# brick_i2c_humidity.net
KiCad netlist of a schematic drawn in EAGLE
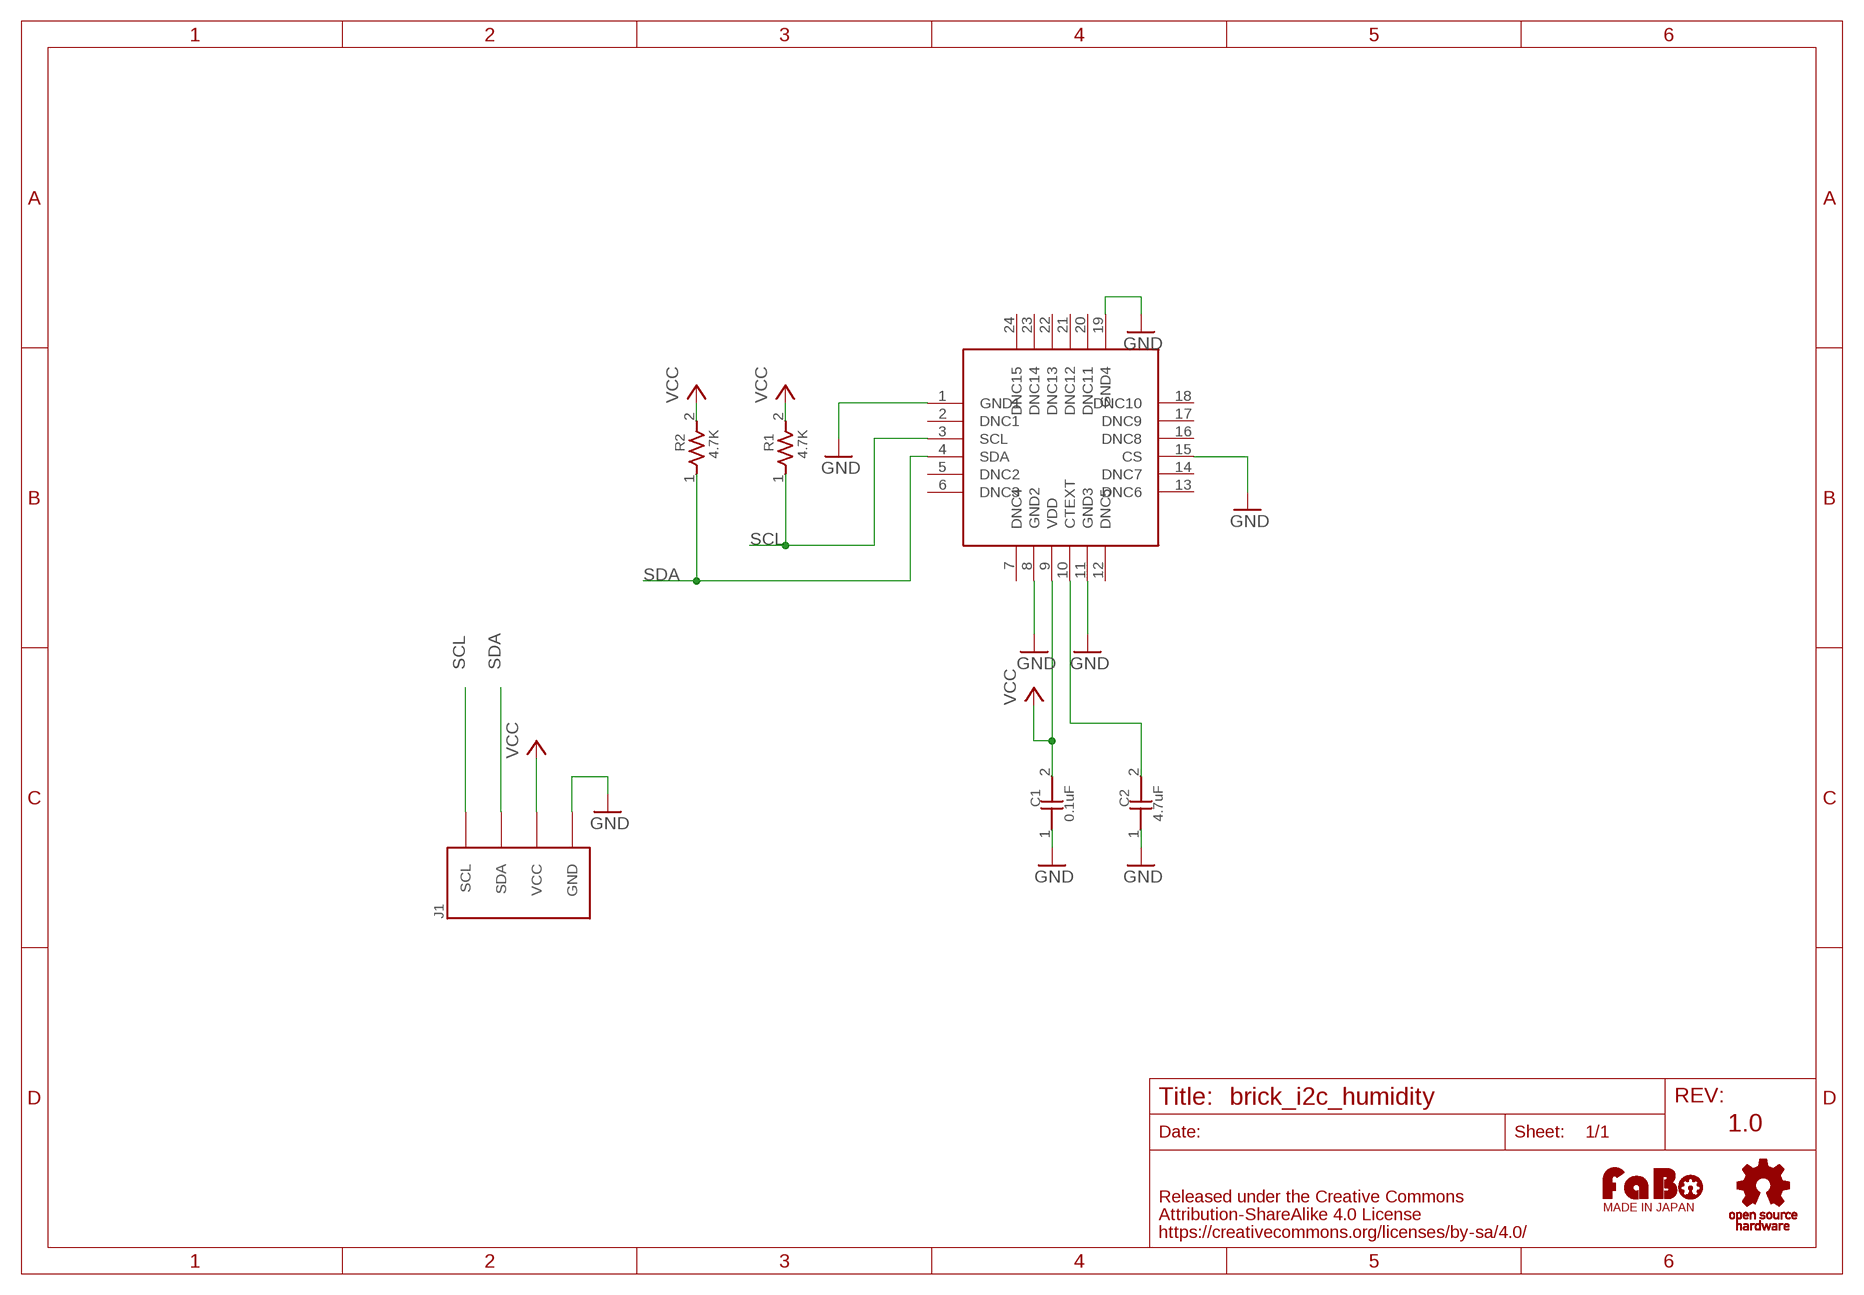
[diagram p0: schematic, sheet 1]

(export (version "E")
  (design (tool "Eeschema 10.0.6"))
  (components
    (comp (ref "C1")
      (value "0.1uF")
      (footprint "eagle-import:0603")
      (libsource (lib "eagle-import") (part "CAPACITOR0603"))
    )
    (comp (ref "C2")
      (value "4.7uF")
      (footprint "eagle-import:0603")
      (libsource (lib "eagle-import") (part "CAPACITOR0603"))
    )
    (comp (ref "J1")
      (value "BRICK_I2C")
      (footprint "eagle-import:BRICK_I2C")
      (libsource (lib "eagle-import") (part "BRICK_I2C"))
    )
    (comp (ref "R1")
      (value "4.7K")
      (footprint "eagle-import:0603")
      (libsource (lib "eagle-import") (part "RESISTOR0603"))
    )
    (comp (ref "R2")
      (value "4.7K")
      (footprint "eagle-import:0603")
      (libsource (lib "eagle-import") (part "RESISTOR0603"))
    )
    (comp (ref "SI1")
      (value "SILICONLAB-SI7005")
      (footprint "eagle-import:SILICONLAB-SI7005")
      (libsource (lib "eagle-import") (part "SILICONLAB-SI7005"))
    )
    (comp (ref "U$2")
      (value "LOGO_FABO-M")
      (footprint "eagle-import:LOGO_FABO_M")
      (libsource (lib "eagle-import") (part "LOGO_FABO-M"))
    )
    (comp (ref "U$4")
      (value "LOGO_OSHW_T-M")
      (footprint "eagle-import:LOGO_OSHW_T_M")
      (libsource (lib "eagle-import") (part "LOGO_OSHW_T-M"))
    )
  )
  (nets
    (net (code "1") (name "/SCL") (class "Default")
      (node (ref "J1") (pin "SCL") (pinfunction "SCL_SCL") (pintype "bidirectional"))
      (node (ref "R1") (pin "1") (pinfunction "1_1") (pintype "passive"))
      (node (ref "SI1") (pin "3") (pinfunction "SCL_3") (pintype "bidirectional"))
    )
    (net (code "2") (name "/SDA") (class "Default")
      (node (ref "J1") (pin "SDA") (pinfunction "SDA_SDA") (pintype "bidirectional"))
      (node (ref "R2") (pin "1") (pinfunction "1_1") (pintype "passive"))
      (node (ref "SI1") (pin "4") (pinfunction "SDA_4") (pintype "bidirectional"))
    )
    (net (code "3") (name "GND") (class "Default")
      (node (ref "C1") (pin "1") (pinfunction "1_1") (pintype "passive"))
      (node (ref "C2") (pin "1") (pinfunction "1_1") (pintype "passive"))
      (node (ref "J1") (pin "GND") (pinfunction "GND_GND") (pintype "bidirectional"))
      (node (ref "SI1") (pin "1") (pinfunction "GND1_1") (pintype "bidirectional"))
      (node (ref "SI1") (pin "11") (pinfunction "GND3_11") (pintype "bidirectional"))
      (node (ref "SI1") (pin "15") (pinfunction "CS_15") (pintype "bidirectional"))
      (node (ref "SI1") (pin "19") (pinfunction "GND4_19") (pintype "bidirectional"))
      (node (ref "SI1") (pin "8") (pinfunction "GND2_8") (pintype "bidirectional"))
    )
    (net (code "4") (name "Net-(SI1-CTEXT)") (class "Default")
      (node (ref "C2") (pin "2") (pinfunction "2_2") (pintype "passive"))
      (node (ref "SI1") (pin "10") (pinfunction "CTEXT_10") (pintype "bidirectional"))
    )
    (net (code "5") (name "VCC") (class "Default")
      (node (ref "C1") (pin "2") (pinfunction "2_2") (pintype "passive"))
      (node (ref "J1") (pin "VCC") (pinfunction "VCC_VCC") (pintype "bidirectional"))
      (node (ref "R1") (pin "2") (pinfunction "2_2") (pintype "passive"))
      (node (ref "R2") (pin "2") (pinfunction "2_2") (pintype "passive"))
      (node (ref "SI1") (pin "9") (pinfunction "VDD_9") (pintype "bidirectional"))
    )
    (net (code "6") (name "unconnected-(SI1-DNC1-Pad2)") (class "Default")
      (node (ref "SI1") (pin "2") (pinfunction "DNC1_2") (pintype "bidirectional"))
    )
    (net (code "7") (name "unconnected-(SI1-DNC2-Pad5)") (class "Default")
      (node (ref "SI1") (pin "5") (pinfunction "DNC2_5") (pintype "bidirectional"))
    )
    (net (code "8") (name "unconnected-(SI1-DNC3-Pad6)") (class "Default")
      (node (ref "SI1") (pin "6") (pinfunction "DNC3_6") (pintype "bidirectional"))
    )
    (net (code "9") (name "unconnected-(SI1-DNC4-Pad7)") (class "Default")
      (node (ref "SI1") (pin "7") (pinfunction "DNC4_7") (pintype "bidirectional"))
    )
    (net (code "10") (name "unconnected-(SI1-DNC5-Pad12)") (class "Default")
      (node (ref "SI1") (pin "12") (pinfunction "DNC5_12") (pintype "bidirectional"))
    )
    (net (code "11") (name "unconnected-(SI1-DNC6-Pad13)") (class "Default")
      (node (ref "SI1") (pin "13") (pinfunction "DNC6_13") (pintype "bidirectional"))
    )
    (net (code "12") (name "unconnected-(SI1-DNC7-Pad14)") (class "Default")
      (node (ref "SI1") (pin "14") (pinfunction "DNC7_14") (pintype "bidirectional"))
    )
    (net (code "13") (name "unconnected-(SI1-DNC8-Pad16)") (class "Default")
      (node (ref "SI1") (pin "16") (pinfunction "DNC8_16") (pintype "bidirectional"))
    )
    (net (code "14") (name "unconnected-(SI1-DNC9-Pad17)") (class "Default")
      (node (ref "SI1") (pin "17") (pinfunction "DNC9_17") (pintype "bidirectional"))
    )
    (net (code "15") (name "unconnected-(SI1-DNC10-Pad18)") (class "Default")
      (node (ref "SI1") (pin "18") (pinfunction "DNC10_18") (pintype "bidirectional"))
    )
    (net (code "16") (name "unconnected-(SI1-DNC11-Pad20)") (class "Default")
      (node (ref "SI1") (pin "20") (pinfunction "DNC11_20") (pintype "bidirectional"))
    )
    (net (code "17") (name "unconnected-(SI1-DNC12-Pad21)") (class "Default")
      (node (ref "SI1") (pin "21") (pinfunction "DNC12_21") (pintype "bidirectional"))
    )
    (net (code "18") (name "unconnected-(SI1-DNC13-Pad22)") (class "Default")
      (node (ref "SI1") (pin "22") (pinfunction "DNC13_22") (pintype "bidirectional"))
    )
    (net (code "19") (name "unconnected-(SI1-DNC14-Pad23)") (class "Default")
      (node (ref "SI1") (pin "23") (pinfunction "DNC14_23") (pintype "bidirectional"))
    )
    (net (code "20") (name "unconnected-(SI1-DNC15-Pad24)") (class "Default")
      (node (ref "SI1") (pin "24") (pinfunction "DNC15_24") (pintype "bidirectional"))
    )
  )
)
